# USB_to_UART.net
KiCad netlist of a schematic drawn in Altium Designer
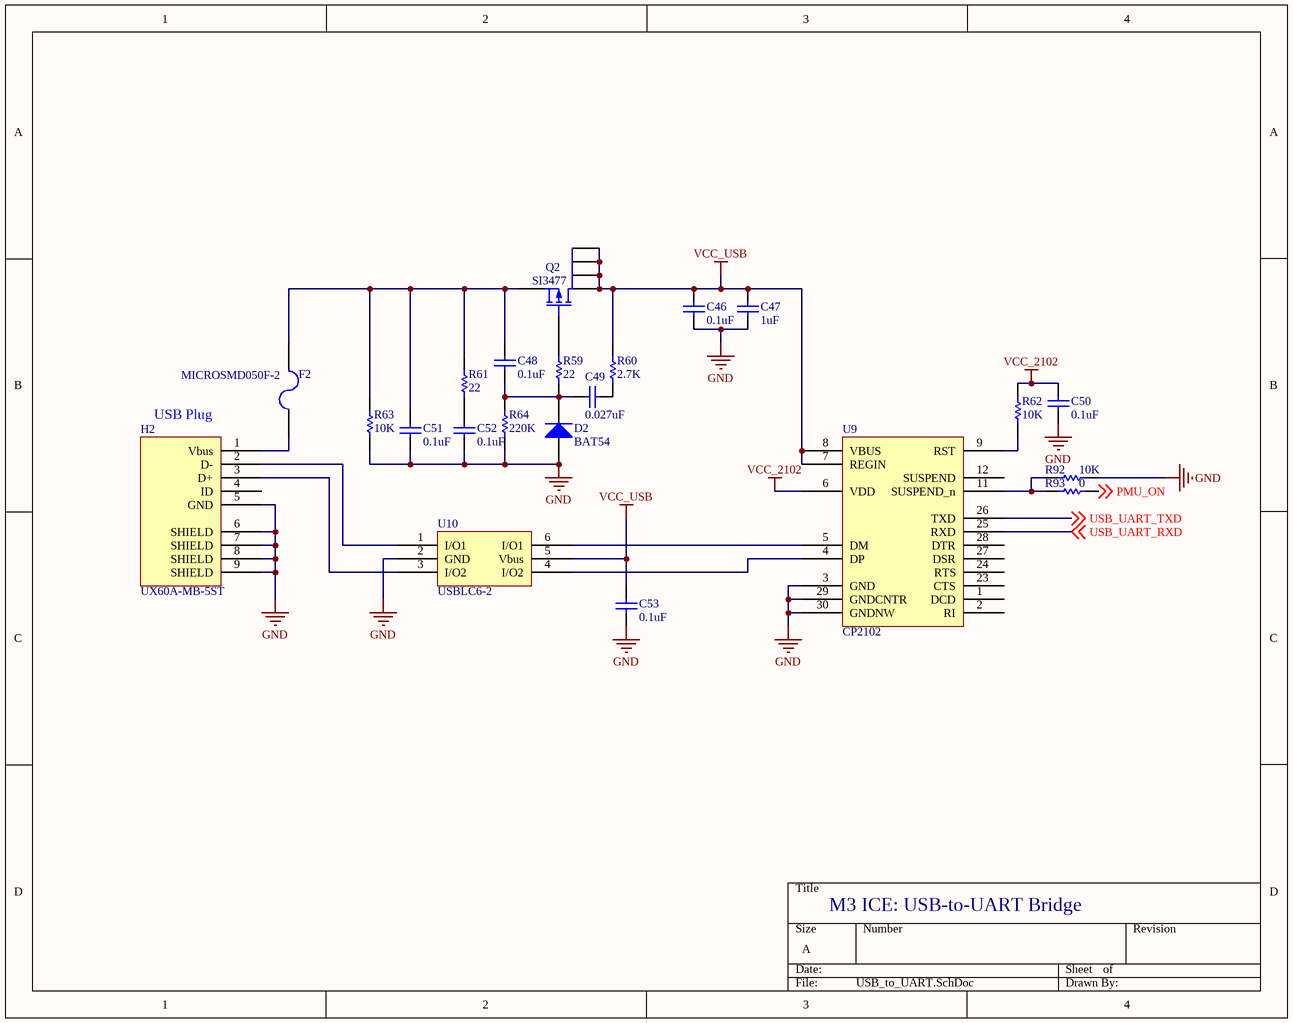
[diagram p0: USB_to_UART.SchDoc]

(export (version "E")
  (design (tool "Eeschema 10.0.6"))
  (components
    (comp (ref "C46")
      (value "0.1uF")
      (footprint "1608[0603]")
      (description "Capacitor (Semiconductor SIM Model)")
      (fields
        (field (name "DISTPARTNO") "445-1317-1-ND")
        (field (name "MANPARTNO") "C1608X7R1C104K")
        (field (name "PUBLISHER") "Altium Limited")
      )
      (libsource (lib "Miscellaneous Devices") (part "Cap Semi"))
    )
    (comp (ref "C47")
      (value "1uF")
      (footprint "1608[0603]")
      (description "Capacitor (Semiconductor SIM Model)")
      (fields
        (field (name "DISTPARTNO") "445-1327-1-ND")
        (field (name "MANPARTNO") "C1608Y5V1C105Z")
        (field (name "PUBLISHER") "Altium Limited")
      )
      (libsource (lib "Miscellaneous Devices") (part "Cap Semi"))
    )
    (comp (ref "C48")
      (value "0.1uF")
      (footprint "1608[0603]")
      (description "Capacitor (Semiconductor SIM Model)")
      (fields
        (field (name "DISTPARTNO") "445-1317-1-ND")
        (field (name "MANPARTNO") "C1608X7R1C104K")
        (field (name "PUBLISHER") "Altium Limited")
      )
      (libsource (lib "Miscellaneous Devices") (part "Cap Semi"))
    )
    (comp (ref "C49")
      (value "0.027uF")
      (footprint "1608[0603]")
      (description "Capacitor (Semiconductor SIM Model)")
      (fields
        (field (name "DISTPARTNO") "478-1232-1-ND")
        (field (name "MANPARTNO") "06035C273KAT2A")
        (field (name "PUBLISHER") "Altium Limited")
      )
      (libsource (lib "Miscellaneous Devices") (part "Cap Semi"))
    )
    (comp (ref "C50")
      (value "0.1uF")
      (footprint "1608[0603]")
      (description "Capacitor (Semiconductor SIM Model)")
      (fields
        (field (name "DISTPARTNO") "445-1317-1-ND")
        (field (name "MANPARTNO") "C1608X7R1C104K")
        (field (name "PUBLISHER") "Altium Limited")
      )
      (libsource (lib "Miscellaneous Devices") (part "Cap Semi"))
    )
    (comp (ref "C51")
      (value "0.1uF")
      (footprint "1608[0603]")
      (description "Capacitor (Semiconductor SIM Model)")
      (fields
        (field (name "DISTPARTNO") "445-1317-1-ND")
        (field (name "MANPARTNO") "C1608X7R1C104K")
        (field (name "PUBLISHER") "Altium Limited")
      )
      (libsource (lib "Miscellaneous Devices") (part "Cap Semi"))
    )
    (comp (ref "C52")
      (value "0.1uF")
      (footprint "1608[0603]")
      (description "Capacitor (Semiconductor SIM Model)")
      (fields
        (field (name "DISTPARTNO") "445-1317-1-ND")
        (field (name "MANPARTNO") "C1608X7R1C104K")
        (field (name "PUBLISHER") "Altium Limited")
      )
      (libsource (lib "Miscellaneous Devices") (part "Cap Semi"))
    )
    (comp (ref "C53")
      (value "0.1uF")
      (footprint "1608[0603]")
      (description "Capacitor (Semiconductor SIM Model)")
      (fields
        (field (name "DISTPARTNO") "445-1317-1-ND")
        (field (name "MANPARTNO") "C1608X7R1C104K")
        (field (name "PUBLISHER") "Altium Limited")
      )
      (libsource (lib "Miscellaneous Devices") (part "Cap Semi"))
    )
    (comp (ref "D2")
      (value "BAT54")
      (footprint "SOT-23_N")
      (description "Low-Loss RF Switching Diode")
      (fields
        (field (name "DISTPARTNO") "BAT54-FDICT-ND")
        (field (name "MANPARTNO") "BAT54-7-F")
        (field (name "PUBLISHER") "Altium Limited")
      )
      (libsource (lib "Miscellaneous Devices") (part "Diode BAT18"))
    )
    (comp (ref "F2")
      (value "MICROSMD050F-2")
      (footprint "1210")
      (description "POLYSWITCH 0.50A RESET FUSE SMD")
      (fields (field (name "DISTPARTNO") "MICROSMD050FCT-ND"))
      (libsource (lib "M3") (part "Fuse MICROSMD050F-2"))
    )
    (comp (ref "H2")
      (value "UX60A-MB-5ST")
      (footprint "USB Mini-B")
      (description "USB mini-B")
      (fields (field (name "DISTPARTNO") "H2961CT-ND"))
      (libsource (lib "M3") (part "UX60-MB-5ST"))
    )
    (comp (ref "Q2")
      (value "SI3477")
      (footprint "TSOP-6")
      (description "P-Channel MOSFET")
      (fields (field (name "DISTPARTNO") "SI3477DV-T1-GE3CT-ND") (field (name "MANPARTNO") "SI3477DV-T1-GE3"))
      (libsource (lib "M3") (part "SI3477"))
    )
    (comp (ref "R59")
      (value "22")
      (footprint "0603")
      (description "Semiconductor Resistor")
      (fields
        (field (name "DISTPARTNO") "P22GCT-ND")
        (field (name "MANPARTNO") "ERJ-3GEYJ220V")
        (field (name "PUBLISHER") "Altium Limited")
      )
      (libsource (lib "M3") (part "Res Chip"))
    )
    (comp (ref "R60")
      (value "2.7K")
      (footprint "0603")
      (description "Semiconductor Resistor")
      (fields
        (field (name "DISTPARTNO") "P2.7KGCT-ND")
        (field (name "MANPARTNO") "ERJ-3GEYJ272V")
        (field (name "PUBLISHER") "Altium Limited")
      )
      (libsource (lib "M3") (part "Res Chip"))
    )
    (comp (ref "R61")
      (value "22")
      (footprint "0603")
      (description "Semiconductor Resistor")
      (fields
        (field (name "DISTPARTNO") "P22GCT-ND")
        (field (name "MANPARTNO") "ERJ-3GEYJ220V")
        (field (name "PUBLISHER") "Altium Limited")
      )
      (libsource (lib "M3") (part "Res Chip"))
    )
    (comp (ref "R62")
      (value "10K")
      (footprint "0603")
      (description "Semiconductor Resistor")
      (fields
        (field (name "DISTPARTNO") "P10KGCT-ND")
        (field (name "MANPARTNO") "ERJ-3GEYJ103V")
        (field (name "PUBLISHER") "Altium Limited")
      )
      (libsource (lib "M3") (part "Res Chip"))
    )
    (comp (ref "R63")
      (value "10K")
      (footprint "0603")
      (description "Semiconductor Resistor")
      (fields
        (field (name "DISTPARTNO") "P10KGCT-ND")
        (field (name "MANPARTNO") "ERJ-3GEYJ103V")
        (field (name "PUBLISHER") "Altium Limited")
      )
      (libsource (lib "M3") (part "Res Chip"))
    )
    (comp (ref "R64")
      (value "220K")
      (footprint "0603")
      (description "Semiconductor Resistor")
      (fields
        (field (name "DISTPARTNO") "P220KGCT-ND")
        (field (name "MANPARTNO") "ERJ-3GEYJ224V")
        (field (name "PUBLISHER") "Altium Limited")
      )
      (libsource (lib "M3") (part "Res Chip"))
    )
    (comp (ref "R92")
      (value "10K")
      (footprint "0402")
      (description "Semiconductor Resistor")
      (fields
        (field (name "DISTPARTNO") "P10.0KLCT-ND")
        (field (name "MANPARTNO") "ERJ-2RKF1002X")
        (field (name "PUBLISHER") "Altium Limited")
      )
      (libsource (lib "M3") (part "Res Chip"))
    )
    (comp (ref "R93")
      (value "0")
      (footprint "0402")
      (description "Semiconductor Resistor")
      (fields
        (field (name "DISTPARTNO") "P0.0JCT-ND")
        (field (name "MANPARTNO") "ERJ-2GE0R00X")
        (field (name "PUBLISHER") "Altium Limited")
      )
      (libsource (lib "M3") (part "Res Chip"))
    )
    (comp (ref "U9")
      (value "CP2102")
      (footprint "QFN-28")
      (fields (field (name "DISTPARTNO") "336-1160-5-ND") (field (name "MANPARTNO") "CP2102-GM"))
      (libsource (lib "M3") (part "CP2102"))
    )
    (comp (ref "U10")
      (value "USBLC6-2")
      (footprint "SOT23-6_L")
      (description "USB ESD Protection")
      (fields (field (name "DISTPARTNO") "497-11882-1-ND") (field (name "MANPARTNO") "USBLC6-2SC6Y"))
      (libsource (lib "M3") (part "USBLC6-2"))
    )
  )
  (nets
    (net (code "1") (name "GND") (class "Default")
      (node (ref "C46") (pin "1") (pinfunction "1_1") (pintype "passive"))
      (node (ref "C47") (pin "1") (pinfunction "1_1") (pintype "passive"))
      (node (ref "C50") (pin "1") (pinfunction "1_1") (pintype "passive"))
      (node (ref "C51") (pin "1") (pinfunction "1_1") (pintype "passive"))
      (node (ref "C52") (pin "1") (pinfunction "1_1") (pintype "passive"))
      (node (ref "C53") (pin "1") (pinfunction "1_1") (pintype "passive"))
      (node (ref "D2") (pin "1") (pinfunction "A_1") (pintype "passive"))
      (node (ref "H2") (pin "5") (pinfunction "GND_5") (pintype "passive"))
      (node (ref "H2") (pin "6") (pinfunction "SHIELD_6") (pintype "passive"))
      (node (ref "H2") (pin "7") (pinfunction "SHIELD_7") (pintype "passive"))
      (node (ref "H2") (pin "8") (pinfunction "SHIELD_8") (pintype "passive"))
      (node (ref "H2") (pin "9") (pinfunction "SHIELD_9") (pintype "passive"))
      (node (ref "R63") (pin "1") (pinfunction "1_1") (pintype "passive"))
      (node (ref "R64") (pin "1") (pinfunction "1_1") (pintype "passive"))
      (node (ref "R92") (pin "2") (pinfunction "2_2") (pintype "passive"))
      (node (ref "U10") (pin "2") (pinfunction "GND_2") (pintype "passive"))
      (node (ref "U9") (pin "29") (pinfunction "GNDCNTR_29") (pintype "passive"))
      (node (ref "U9") (pin "3") (pinfunction "GND_3") (pintype "passive"))
      (node (ref "U9") (pin "30") (pinfunction "GNDNW_30") (pintype "passive"))
    )
    (net (code "2") (name "Net-(C49-Pad1)") (class "Default")
      (node (ref "C49") (pin "1") (pinfunction "1_1") (pintype "passive"))
      (node (ref "R60") (pin "1") (pinfunction "1_1") (pintype "passive"))
    )
    (net (code "3") (name "Net-(C52-Pad2)") (class "Default")
      (node (ref "C52") (pin "2") (pinfunction "2_2") (pintype "passive"))
      (node (ref "R61") (pin "1") (pinfunction "1_1") (pintype "passive"))
    )
    (net (code "4") (name "Net-(D2-K)") (class "Default")
      (node (ref "C48") (pin "1") (pinfunction "1_1") (pintype "passive"))
      (node (ref "C49") (pin "2") (pinfunction "2_2") (pintype "passive"))
      (node (ref "D2") (pin "3") (pinfunction "K_3") (pintype "passive"))
      (node (ref "R59") (pin "1") (pinfunction "1_1") (pintype "passive"))
      (node (ref "R64") (pin "2") (pinfunction "2_2") (pintype "passive"))
    )
    (net (code "5") (name "Net-(H2-D+)") (class "Default")
      (node (ref "H2") (pin "3") (pinfunction "D+_3") (pintype "passive"))
      (node (ref "U10") (pin "3") (pinfunction "I/O2_3") (pintype "passive"))
    )
    (net (code "6") (name "Net-(H2-D-)") (class "Default")
      (node (ref "H2") (pin "2") (pinfunction "D-_2") (pintype "passive"))
      (node (ref "U10") (pin "1") (pinfunction "I/O1_1") (pintype "passive"))
    )
    (net (code "7") (name "Net-(H2-Vbus)") (class "Default")
      (node (ref "F2") (pin "1") (pinfunction "1_1") (pintype "passive"))
      (node (ref "H2") (pin "1") (pinfunction "Vbus_1") (pintype "passive"))
    )
    (net (code "8") (name "Net-(Q2-G)") (class "Default")
      (node (ref "Q2") (pin "3") (pinfunction "G_3") (pintype "passive"))
      (node (ref "R59") (pin "2") (pinfunction "2_2") (pintype "passive"))
    )
    (net (code "9") (name "Net-(Q2-S)") (class "Default")
      (node (ref "C48") (pin "2") (pinfunction "2_2") (pintype "passive"))
      (node (ref "C51") (pin "2") (pinfunction "2_2") (pintype "passive"))
      (node (ref "F2") (pin "2") (pinfunction "2_2") (pintype "passive"))
      (node (ref "Q2") (pin "4") (pinfunction "S_4") (pintype "passive"))
      (node (ref "R61") (pin "2") (pinfunction "2_2") (pintype "passive"))
      (node (ref "R63") (pin "2") (pinfunction "2_2") (pintype "passive"))
    )
    (net (code "10") (name "Net-(U9-DM)") (class "Default")
      (node (ref "U10") (pin "6") (pinfunction "I/O1_6") (pintype "passive"))
      (node (ref "U9") (pin "5") (pinfunction "DM_5") (pintype "passive"))
    )
    (net (code "11") (name "Net-(U9-DP)") (class "Default")
      (node (ref "U10") (pin "4") (pinfunction "I/O2_4") (pintype "passive"))
      (node (ref "U9") (pin "4") (pinfunction "DP_4") (pintype "passive"))
    )
    (net (code "12") (name "Net-(U9-RST)") (class "Default")
      (node (ref "R62") (pin "1") (pinfunction "1_1") (pintype "passive"))
      (node (ref "U9") (pin "9") (pinfunction "RST_9") (pintype "passive"))
    )
    (net (code "13") (name "Net-(U9-SUSPEND_n)") (class "Default")
      (node (ref "R92") (pin "1") (pinfunction "1_1") (pintype "passive"))
      (node (ref "R93") (pin "1") (pinfunction "1_1") (pintype "passive"))
      (node (ref "U9") (pin "11") (pinfunction "SUSPEND_n_11") (pintype "passive"))
    )
    (net (code "14") (name "PMU_ON") (class "Default")
      (node (ref "R93") (pin "2") (pinfunction "2_2") (pintype "passive"))
    )
    (net (code "15") (name "USB_UART_RXD") (class "Default")
      (node (ref "U9") (pin "25") (pinfunction "RXD_25") (pintype "passive"))
    )
    (net (code "16") (name "USB_UART_TXD") (class "Default")
      (node (ref "U9") (pin "26") (pinfunction "TXD_26") (pintype "passive"))
    )
    (net (code "17") (name "VCC_2102") (class "Default")
      (node (ref "C50") (pin "2") (pinfunction "2_2") (pintype "passive"))
      (node (ref "R62") (pin "2") (pinfunction "2_2") (pintype "passive"))
      (node (ref "U9") (pin "6") (pinfunction "VDD_6") (pintype "passive"))
    )
    (net (code "18") (name "VCC_USB") (class "Default")
      (node (ref "C46") (pin "2") (pinfunction "2_2") (pintype "passive"))
      (node (ref "C47") (pin "2") (pinfunction "2_2") (pintype "passive"))
      (node (ref "C53") (pin "2") (pinfunction "2_2") (pintype "passive"))
      (node (ref "Q2") (pin "1") (pinfunction "D_1") (pintype "passive"))
      (node (ref "Q2") (pin "2") (pinfunction "D_2") (pintype "passive"))
      (node (ref "Q2") (pin "5") (pinfunction "D_5") (pintype "passive"))
      (node (ref "Q2") (pin "6") (pinfunction "D_6") (pintype "passive"))
      (node (ref "R60") (pin "2") (pinfunction "2_2") (pintype "passive"))
      (node (ref "U10") (pin "5") (pinfunction "Vbus_5") (pintype "passive"))
      (node (ref "U9") (pin "7") (pinfunction "REGIN_7") (pintype "passive"))
      (node (ref "U9") (pin "8") (pinfunction "VBUS_8") (pintype "passive"))
    )
    (net (code "19") (name "unconnected-(H2-ID-Pad4)") (class "Default")
      (node (ref "H2") (pin "4") (pinfunction "ID_4") (pintype "passive"))
    )
    (net (code "20") (name "unconnected-(U9-CTS-Pad23)") (class "Default")
      (node (ref "U9") (pin "23") (pinfunction "CTS_23") (pintype "passive"))
    )
    (net (code "21") (name "unconnected-(U9-DCD-Pad1)") (class "Default")
      (node (ref "U9") (pin "1") (pinfunction "DCD_1") (pintype "passive"))
    )
    (net (code "22") (name "unconnected-(U9-DSR-Pad27)") (class "Default")
      (node (ref "U9") (pin "27") (pinfunction "DSR_27") (pintype "passive"))
    )
    (net (code "23") (name "unconnected-(U9-DTR-Pad28)") (class "Default")
      (node (ref "U9") (pin "28") (pinfunction "DTR_28") (pintype "passive"))
    )
    (net (code "24") (name "unconnected-(U9-RI-Pad2)") (class "Default")
      (node (ref "U9") (pin "2") (pinfunction "RI_2") (pintype "passive"))
    )
    (net (code "25") (name "unconnected-(U9-RTS-Pad24)") (class "Default")
      (node (ref "U9") (pin "24") (pinfunction "RTS_24") (pintype "passive"))
    )
    (net (code "26") (name "unconnected-(U9-SUSPEND-Pad12)") (class "Default")
      (node (ref "U9") (pin "12") (pinfunction "SUSPEND_12") (pintype "passive"))
    )
  )
)
